# Cap-Touch.net
KiCad netlist of a schematic drawn in Altium Designer
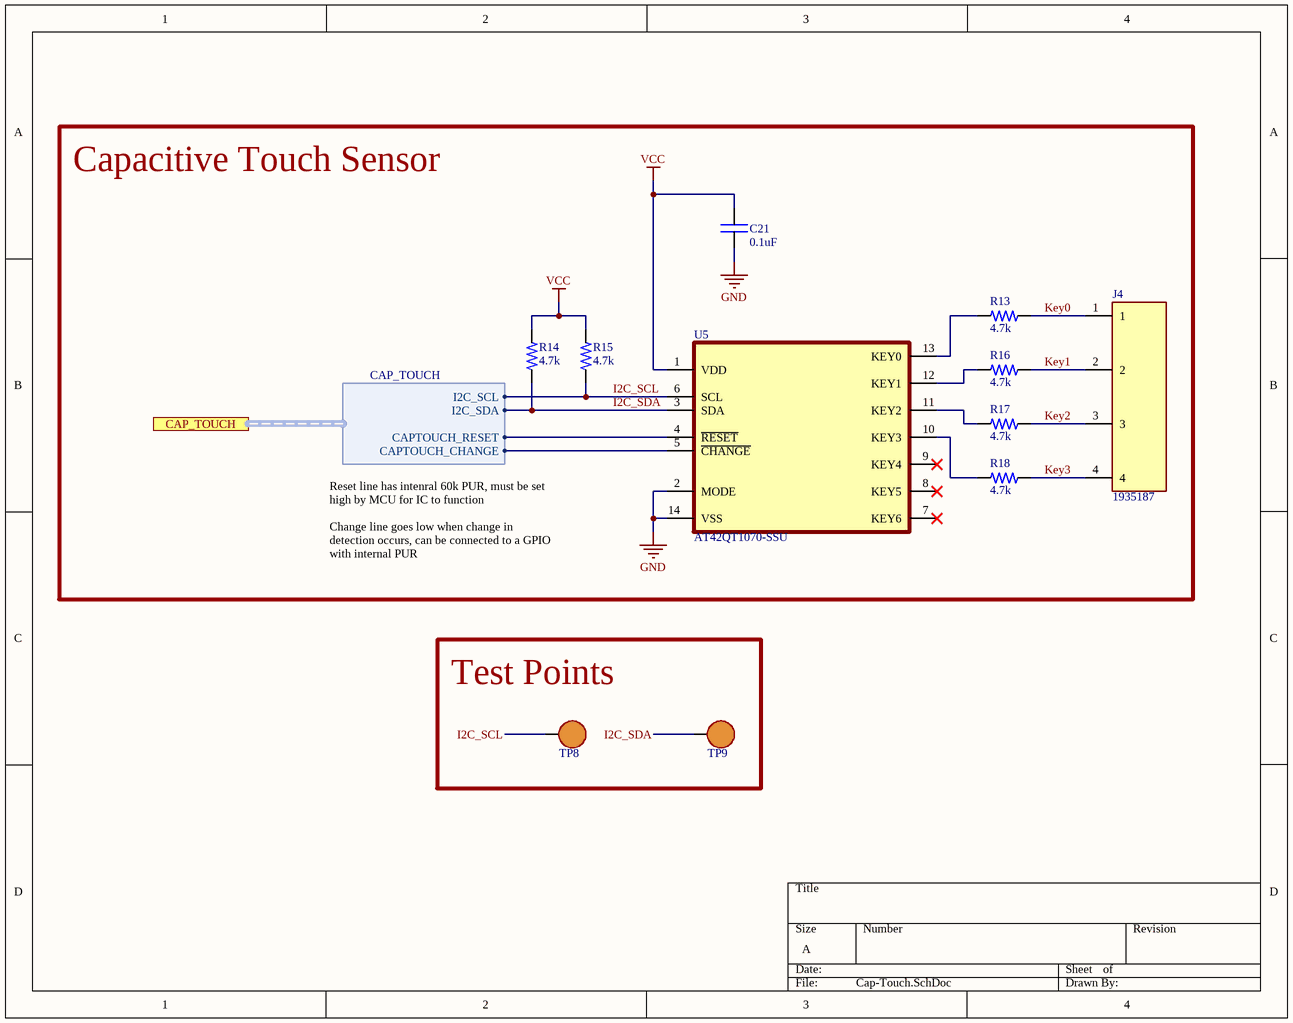
[diagram p0: Cap-Touch.SchDoc]

(export (version "E")
  (design (tool "Eeschema 10.0.6"))
  (components
    (comp (ref "C21")
      (value "0.1uF")
      (footprint "Beethoven-clock:0402C")
      (description "Capacitor")
      (fields (field (name "MFR") "Murata Electronics") (field (name "Comment") "CAP"))
      (libsource (lib "Beethoven-clock") (part "CAP"))
    )
    (comp (ref "J4")
      (value "1935187")
      (footprint "Beethoven-clock:1935187")
      (description "Fixed Terminal Blocks PT 1.5/4-5.0-H")
      (fields (field (name "MFR") "Phoenix Contact"))
      (libsource (lib "Beethoven-clock") (part "SCREW CONN 4 POS"))
    )
    (comp (ref "R13")
      (value "4.7k")
      (footprint "Beethoven-clock:0402R")
      (description "Resistor")
      (fields (field (name "MFR") "YAGEO") (field (name "Comment") "RES"))
      (libsource (lib "Beethoven-clock") (part "RES"))
    )
    (comp (ref "R14")
      (value "4.7k")
      (footprint "Beethoven-clock:0402R")
      (description "Resistor")
      (fields (field (name "MFR") "YAGEO") (field (name "Comment") "RES"))
      (libsource (lib "Beethoven-clock") (part "RES"))
    )
    (comp (ref "R15")
      (value "4.7k")
      (footprint "Beethoven-clock:0402R")
      (description "Resistor")
      (fields (field (name "MFR") "YAGEO") (field (name "Comment") "RES"))
      (libsource (lib "Beethoven-clock") (part "RES"))
    )
    (comp (ref "R16")
      (value "4.7k")
      (footprint "Beethoven-clock:0402R")
      (description "Resistor")
      (fields (field (name "MFR") "YAGEO") (field (name "Comment") "RES"))
      (libsource (lib "Beethoven-clock") (part "RES"))
    )
    (comp (ref "R17")
      (value "4.7k")
      (footprint "Beethoven-clock:0402R")
      (description "Resistor")
      (fields (field (name "MFR") "YAGEO") (field (name "Comment") "RES"))
      (libsource (lib "Beethoven-clock") (part "RES"))
    )
    (comp (ref "R18")
      (value "4.7k")
      (footprint "Beethoven-clock:0402R")
      (description "Resistor")
      (fields (field (name "MFR") "YAGEO") (field (name "Comment") "RES"))
      (libsource (lib "Beethoven-clock") (part "RES"))
    )
    (comp (ref "TP8")
      (value "RCWCTE")
      (footprint "Beethoven-clock:RCWCTE")
      (description "Test Point, Surface Mount")
      (fields (field (name "MFR") "KOA Speer Electronics, Inc."))
      (libsource (lib "Beethoven-clock") (part "TEST POINT"))
    )
    (comp (ref "TP9")
      (value "RCWCTE")
      (footprint "Beethoven-clock:RCWCTE")
      (description "Test Point, Surface Mount")
      (fields (field (name "MFR") "KOA Speer Electronics, Inc."))
      (libsource (lib "Beethoven-clock") (part "TEST POINT"))
    )
    (comp (ref "U5")
      (value "AT42QT1070-SSU")
      (footprint "Beethoven-clock:14-SOIC")
      (description "Capacitive Touch Buttons 14-SOIC")
      (fields (field (name "MFR") "Microchip"))
      (libsource (lib "Beethoven-clock") (part "AT42QT1070-SSU"))
    )
  )
  (nets
    (net (code "2") (name "/CAPTOUCH_CHANGE") (class "Default")
      (node (ref "U5") (pin "5") (pinfunction "~{CHANGE}_5") (pintype "passive"))
    )
    (net (code "3") (name "/CAPTOUCH_RESET") (class "Default")
      (node (ref "U5") (pin "4") (pinfunction "~{RESET}_4") (pintype "passive"))
    )
    (net (code "4") (name "/I2C_SCL") (class "Default")
      (node (ref "R15") (pin "1") (pinfunction "1_1") (pintype "passive"))
      (node (ref "TP8") (pin "1") (pinfunction "0_1") (pintype "passive"))
      (node (ref "U5") (pin "6") (pinfunction "SCL_6") (pintype "passive"))
    )
    (net (code "5") (name "/I2C_SDA") (class "Default")
      (node (ref "R14") (pin "1") (pinfunction "1_1") (pintype "passive"))
      (node (ref "TP9") (pin "1") (pinfunction "0_1") (pintype "passive"))
      (node (ref "U5") (pin "3") (pinfunction "SDA_3") (pintype "passive"))
    )
    (net (code "6") (name "/Key0") (class "Default")
      (node (ref "J4") (pin "1") (pinfunction "1_1") (pintype "passive"))
      (node (ref "R13") (pin "1") (pinfunction "1_1") (pintype "passive"))
    )
    (net (code "7") (name "/Key1") (class "Default")
      (node (ref "J4") (pin "2") (pinfunction "2_2") (pintype "passive"))
      (node (ref "R16") (pin "1") (pinfunction "1_1") (pintype "passive"))
    )
    (net (code "8") (name "/Key2") (class "Default")
      (node (ref "J4") (pin "3") (pinfunction "3_3") (pintype "passive"))
      (node (ref "R17") (pin "1") (pinfunction "1_1") (pintype "passive"))
    )
    (net (code "9") (name "/Key3") (class "Default")
      (node (ref "J4") (pin "4") (pinfunction "4_4") (pintype "passive"))
      (node (ref "R18") (pin "1") (pinfunction "1_1") (pintype "passive"))
    )
    (net (code "11") (name "GND") (class "Default")
      (node (ref "C21") (pin "1") (pinfunction "1_1") (pintype "passive"))
      (node (ref "U5") (pin "14") (pinfunction "VSS_14") (pintype "passive"))
      (node (ref "U5") (pin "2") (pinfunction "MODE_2") (pintype "passive"))
    )
    (net (code "12") (name "Net-(U5-KEY0)") (class "Default")
      (node (ref "R13") (pin "2") (pinfunction "2_2") (pintype "passive"))
      (node (ref "U5") (pin "13") (pinfunction "KEY0_13") (pintype "passive"))
    )
    (net (code "13") (name "Net-(U5-KEY1)") (class "Default")
      (node (ref "R16") (pin "2") (pinfunction "2_2") (pintype "passive"))
      (node (ref "U5") (pin "12") (pinfunction "KEY1_12") (pintype "passive"))
    )
    (net (code "14") (name "Net-(U5-KEY2)") (class "Default")
      (node (ref "R17") (pin "2") (pinfunction "2_2") (pintype "passive"))
      (node (ref "U5") (pin "11") (pinfunction "KEY2_11") (pintype "passive"))
    )
    (net (code "15") (name "Net-(U5-KEY3)") (class "Default")
      (node (ref "R18") (pin "2") (pinfunction "2_2") (pintype "passive"))
      (node (ref "U5") (pin "10") (pinfunction "KEY3_10") (pintype "passive"))
    )
    (net (code "16") (name "VCC") (class "Default")
      (node (ref "C21") (pin "2") (pinfunction "2_2") (pintype "passive"))
      (node (ref "R14") (pin "2") (pinfunction "2_2") (pintype "passive"))
      (node (ref "R15") (pin "2") (pinfunction "2_2") (pintype "passive"))
      (node (ref "U5") (pin "1") (pinfunction "VDD_1") (pintype "passive"))
    )
    (net (code "17") (name "unconnected-(U5-KEY4-Pad9)") (class "Default")
      (node (ref "U5") (pin "9") (pinfunction "KEY4_9") (pintype "passive+no_connect"))
    )
    (net (code "18") (name "unconnected-(U5-KEY5-Pad8)") (class "Default")
      (node (ref "U5") (pin "8") (pinfunction "KEY5_8") (pintype "passive+no_connect"))
    )
    (net (code "19") (name "unconnected-(U5-KEY6-Pad7)") (class "Default")
      (node (ref "U5") (pin "7") (pinfunction "KEY6_7") (pintype "passive+no_connect"))
    )
  )
)
